# Snickerdoodle_FPGA_JC.net
KiCad netlist of a schematic drawn in Altium Designer
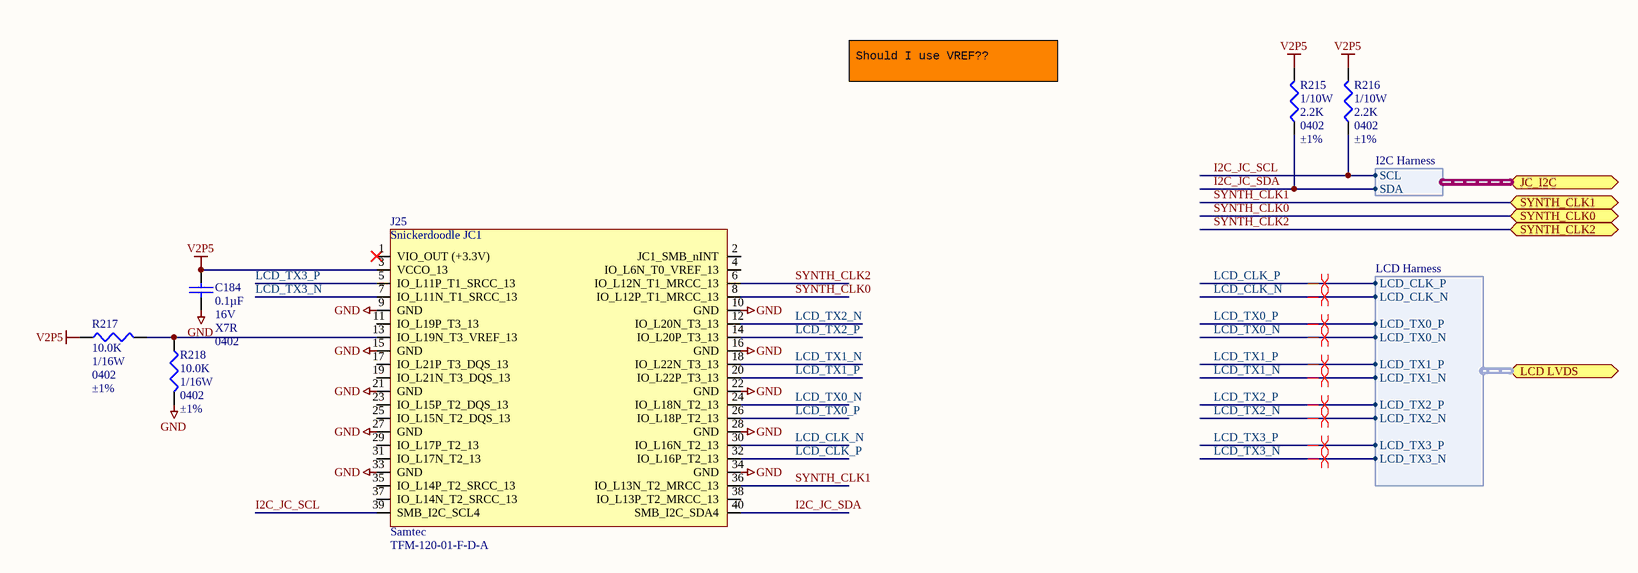
[diagram p0: Snickerdoodle FPGA JC.SchDoc]

(export (version "E")
  (design (tool "Eeschema 10.0.6"))
  (components
    (comp (ref "C184")
      (value "0.1uF")
      (footprint "C_0402")
      (description "CAP CER .10UF 16V X7R 0402")
      (fields
        (field (name "MANUFACTURER") "Murata Electronics North America")
        (field (name "MANUFACTURER PART NUMBER") "GRM155R71C104KA88J")
        (field (name "CAPACITANCE") "0.1µF")
        (field (name "VOLTAGE - RATED") "16V")
        (field (name "TEMPERATURE COEFFICIENT") "X7R")
        (field (name "PACKAGE / CASE") "0402")
      )
      (libsource (lib "Main LibraryX") (part "C_0402_0.1UF_16V"))
    )
    (comp (ref "J25")
      (value "J_SNICKERDOODLE_JC1")
      (footprint "TFM12001-X-D-A")
      (description "SNICKERDOODLE JC1")
      (fields
        (field (name "MANUFACTURER") "Samtec")
        (field (name "MANUFACTURER PART NUMBER") "TFM-120-01-F-D-A")
      )
      (libsource (lib "Cospan Design") (part "J_SNICKERDOODLE_JC1"))
    )
    (comp (ref "R215")
      (value "2.2k Ohms")
      (footprint "R_0402")
      (description "RES 2.20K OHM 1/10W 1% 0402 SMD")
      (fields
        (field (name "MANUFACTURER") "Yageo")
        (field (name "MANUFACTURER PART NUMBER") "RC0402FR-072K2L")
        (field (name "POWER (WATTS)") "1/10W")
        (field (name "RESISTANCE IN OHMS") "2.2K")
        (field (name "CASE") "0402")
        (field (name "TOLERANCE") "±1%")
      )
      (libsource (lib "Main Library") (part "R_0402_2.2K"))
    )
    (comp (ref "R216")
      (value "2.2k Ohms")
      (footprint "R_0402")
      (description "RES 2.20K OHM 1/10W 1% 0402 SMD")
      (fields
        (field (name "MANUFACTURER") "Yageo")
        (field (name "MANUFACTURER PART NUMBER") "RC0402FR-072K2L")
        (field (name "POWER (WATTS)") "1/10W")
        (field (name "RESISTANCE IN OHMS") "2.2K")
        (field (name "CASE") "0402")
        (field (name "TOLERANCE") "±1%")
      )
      (libsource (lib "Main Library") (part "R_0402_2.2K"))
    )
    (comp (ref "R217")
      (value "R_0402_10.0K")
      (footprint "R_0402")
      (description "RES 10.0K OHM 1/16W 1% 0402 SMD")
      (fields
        (field (name "MANUFACTURER") "Stackpole Electronics Inc")
        (field (name "MANUFACTURER PART NUMBER") "RMCF0402FT10K0")
        (field (name "RESISTANCE IN OHMS") "10.0K")
        (field (name "POWER (WATTS)") "1/16W")
        (field (name "CASE") "0402")
        (field (name "TOLERANCE") "±1%")
      )
      (libsource (lib "Main Library") (part "R_0402_10.0K"))
    )
    (comp (ref "R218")
      (value "R_0402_10.0K")
      (footprint "R_0402")
      (description "RES 10.0K OHM 1/16W 1% 0402 SMD")
      (fields
        (field (name "MANUFACTURER") "Stackpole Electronics Inc")
        (field (name "MANUFACTURER PART NUMBER") "RMCF0402FT10K0")
        (field (name "RESISTANCE IN OHMS") "10.0K")
        (field (name "POWER (WATTS)") "1/16W")
        (field (name "CASE") "0402")
        (field (name "TOLERANCE") "±1%")
      )
      (libsource (lib "Main Library") (part "R_0402_10.0K"))
    )
  )
  (nets
    (net (code "4") (name "/I2C_JC_SCL") (class "Default")
      (node (ref "J25") (pin "39") (pinfunction "SMB_I2C_SCL4_39") (pintype "passive"))
      (node (ref "R216") (pin "2") (pinfunction "2_2") (pintype "passive"))
    )
    (net (code "5") (name "/I2C_JC_SDA") (class "Default")
      (node (ref "J25") (pin "40") (pinfunction "SMB_I2C_SDA4_40") (pintype "passive"))
      (node (ref "R215") (pin "2") (pinfunction "2_2") (pintype "passive"))
    )
    (net (code "6") (name "/LCD_CLK_N") (class "Default")
      (node (ref "J25") (pin "30") (pinfunction "IO_L16N_T2_13_30") (pintype "passive"))
    )
    (net (code "7") (name "/LCD_CLK_P") (class "Default")
      (node (ref "J25") (pin "32") (pinfunction "IO_L16P_T2_13_32") (pintype "passive"))
    )
    (net (code "8") (name "/LCD_TX0_N") (class "Default")
      (node (ref "J25") (pin "24") (pinfunction "IO_L18N_T2_13_24") (pintype "passive"))
    )
    (net (code "9") (name "/LCD_TX0_P") (class "Default")
      (node (ref "J25") (pin "26") (pinfunction "IO_L18P_T2_13_26") (pintype "passive"))
    )
    (net (code "10") (name "/LCD_TX1_N") (class "Default")
      (node (ref "J25") (pin "18") (pinfunction "IO_L22N_T3_13_18") (pintype "passive"))
    )
    (net (code "11") (name "/LCD_TX1_P") (class "Default")
      (node (ref "J25") (pin "20") (pinfunction "IO_L22P_T3_13_20") (pintype "passive"))
    )
    (net (code "12") (name "/LCD_TX2_N") (class "Default")
      (node (ref "J25") (pin "12") (pinfunction "IO_L20N_T3_13_12") (pintype "passive"))
    )
    (net (code "13") (name "/LCD_TX2_P") (class "Default")
      (node (ref "J25") (pin "14") (pinfunction "IO_L20P_T3_13_14") (pintype "passive"))
    )
    (net (code "14") (name "/LCD_TX3_N") (class "Default")
      (node (ref "J25") (pin "7") (pinfunction "IO_L11N_T1_SRCC_13_7") (pintype "passive"))
    )
    (net (code "15") (name "/LCD_TX3_P") (class "Default")
      (node (ref "J25") (pin "5") (pinfunction "IO_L11P_T1_SRCC_13_5") (pintype "passive"))
    )
    (net (code "16") (name "/SYNTH_CLK0") (class "Default")
      (node (ref "J25") (pin "8") (pinfunction "IO_L12P_T1_MRCC_13_8") (pintype "passive"))
    )
    (net (code "17") (name "/SYNTH_CLK1") (class "Default")
      (node (ref "J25") (pin "36") (pinfunction "IO_L13N_T2_MRCC_13_36") (pintype "passive"))
    )
    (net (code "18") (name "/SYNTH_CLK2") (class "Default")
      (node (ref "J25") (pin "6") (pinfunction "IO_L12N_T1_MRCC_13_6") (pintype "passive"))
    )
    (net (code "21") (name "GND") (class "Default")
      (node (ref "C184") (pin "1") (pinfunction "1_1") (pintype "passive"))
      (node (ref "J25") (pin "10") (pinfunction "GND_10") (pintype "passive"))
      (node (ref "J25") (pin "15") (pinfunction "GND_15") (pintype "passive"))
      (node (ref "J25") (pin "16") (pinfunction "GND_16") (pintype "passive"))
      (node (ref "J25") (pin "21") (pinfunction "GND_21") (pintype "passive"))
      (node (ref "J25") (pin "22") (pinfunction "GND_22") (pintype "passive"))
      (node (ref "J25") (pin "27") (pinfunction "GND_27") (pintype "passive"))
      (node (ref "J25") (pin "28") (pinfunction "GND_28") (pintype "passive"))
      (node (ref "J25") (pin "33") (pinfunction "GND_33") (pintype "passive"))
      (node (ref "J25") (pin "34") (pinfunction "GND_34") (pintype "passive"))
      (node (ref "J25") (pin "9") (pinfunction "GND_9") (pintype "passive"))
      (node (ref "R218") (pin "1") (pinfunction "1_1") (pintype "passive"))
    )
    (net (code "22") (name "Net-(J25-IO_L19N_T3_VREF_13)") (class "Default")
      (node (ref "J25") (pin "13") (pinfunction "IO_L19N_T3_VREF_13_13") (pintype "passive"))
      (node (ref "R217") (pin "1") (pinfunction "1_1") (pintype "passive"))
      (node (ref "R218") (pin "2") (pinfunction "2_2") (pintype "passive"))
    )
    (net (code "23") (name "V2P5") (class "Default")
      (node (ref "C184") (pin "2") (pinfunction "2_2") (pintype "passive"))
      (node (ref "J25") (pin "3") (pinfunction "VCCO_13_3") (pintype "passive"))
      (node (ref "R215") (pin "1") (pinfunction "1_1") (pintype "passive"))
      (node (ref "R216") (pin "1") (pinfunction "1_1") (pintype "passive"))
      (node (ref "R217") (pin "2") (pinfunction "2_2") (pintype "passive"))
    )
    (net (code "24") (name "unconnected-(J25-IO_L6N_T0_VREF_13-Pad4)") (class "Default")
      (node (ref "J25") (pin "4") (pinfunction "IO_L6N_T0_VREF_13_4") (pintype "passive"))
    )
    (net (code "25") (name "unconnected-(J25-IO_L13P_T2_MRCC_13-Pad38)") (class "Default")
      (node (ref "J25") (pin "38") (pinfunction "IO_L13P_T2_MRCC_13_38") (pintype "passive"))
    )
    (net (code "26") (name "unconnected-(J25-IO_L14N_T2_SRCC_13-Pad37)") (class "Default")
      (node (ref "J25") (pin "37") (pinfunction "IO_L14N_T2_SRCC_13_37") (pintype "passive"))
    )
    (net (code "27") (name "unconnected-(J25-IO_L14P_T2_SRCC_13-Pad35)") (class "Default")
      (node (ref "J25") (pin "35") (pinfunction "IO_L14P_T2_SRCC_13_35") (pintype "passive"))
    )
    (net (code "28") (name "unconnected-(J25-IO_L15N_T2_DQS_13-Pad25)") (class "Default")
      (node (ref "J25") (pin "25") (pinfunction "IO_L15N_T2_DQS_13_25") (pintype "passive"))
    )
    (net (code "29") (name "unconnected-(J25-IO_L15P_T2_DQS_13-Pad23)") (class "Default")
      (node (ref "J25") (pin "23") (pinfunction "IO_L15P_T2_DQS_13_23") (pintype "passive"))
    )
    (net (code "30") (name "unconnected-(J25-IO_L17N_T2_13-Pad31)") (class "Default")
      (node (ref "J25") (pin "31") (pinfunction "IO_L17N_T2_13_31") (pintype "passive"))
    )
    (net (code "31") (name "unconnected-(J25-IO_L17P_T2_13-Pad29)") (class "Default")
      (node (ref "J25") (pin "29") (pinfunction "IO_L17P_T2_13_29") (pintype "passive"))
    )
    (net (code "32") (name "unconnected-(J25-IO_L19P_T3_13-Pad11)") (class "Default")
      (node (ref "J25") (pin "11") (pinfunction "IO_L19P_T3_13_11") (pintype "passive"))
    )
    (net (code "33") (name "unconnected-(J25-IO_L21N_T3_DQS_13-Pad19)") (class "Default")
      (node (ref "J25") (pin "19") (pinfunction "IO_L21N_T3_DQS_13_19") (pintype "passive"))
    )
    (net (code "34") (name "unconnected-(J25-IO_L21P_T3_DQS_13-Pad17)") (class "Default")
      (node (ref "J25") (pin "17") (pinfunction "IO_L21P_T3_DQS_13_17") (pintype "passive"))
    )
    (net (code "35") (name "unconnected-(J25-JC1_SMB_nINT-Pad2)") (class "Default")
      (node (ref "J25") (pin "2") (pinfunction "JC1_SMB_nINT_2") (pintype "passive"))
    )
    (net (code "36") (name "unconnected-(J25-VIO_OUT_(+3.3V)-Pad1)") (class "Default")
      (node (ref "J25") (pin "1") (pinfunction "VIO_OUT_(+3.3V)_1") (pintype "passive+no_connect"))
    )
  )
)
